# pc_tinyecg_max30001.net
KiCad netlist of a schematic drawn in EAGLE
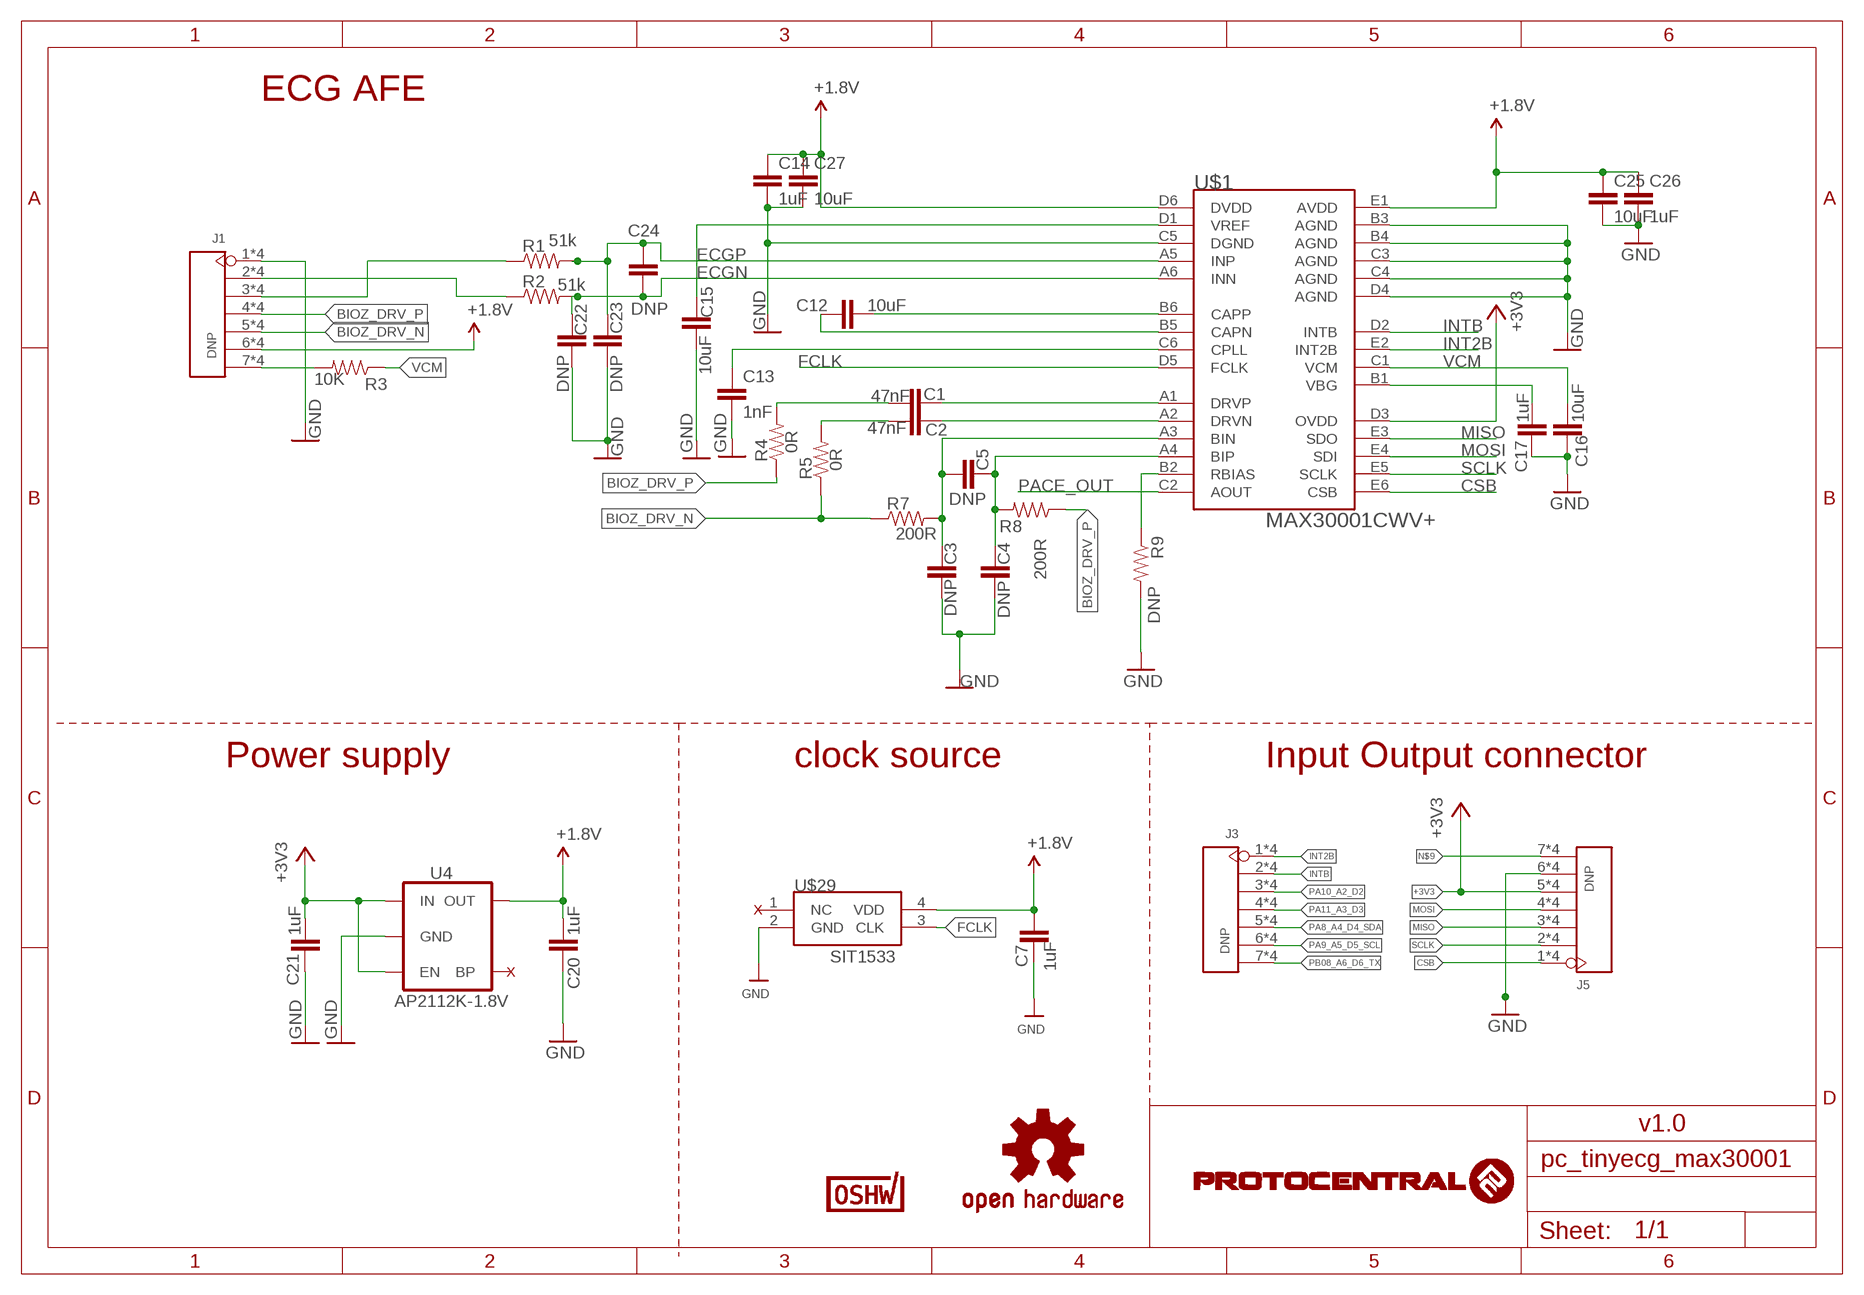
[diagram p0: schematic, sheet 1]

(export (version "E")
  (design (tool "Eeschema 10.0.6"))
  (components
    (comp (ref "C1")
      (value "47nF")
      (footprint "eagle-import:C0402")
      (libsource (lib "eagle-import") (part "C-EUC0402"))
    )
    (comp (ref "C2")
      (value "47nF")
      (footprint "eagle-import:C0402")
      (libsource (lib "eagle-import") (part "C-EUC0402"))
    )
    (comp (ref "C3")
      (value "DNP")
      (footprint "eagle-import:C0402")
      (libsource (lib "eagle-import") (part "C-EUC0402"))
    )
    (comp (ref "C4")
      (value "DNP")
      (footprint "eagle-import:C0402")
      (libsource (lib "eagle-import") (part "C-EUC0402"))
    )
    (comp (ref "C5")
      (value "DNP")
      (footprint "eagle-import:C0402")
      (libsource (lib "eagle-import") (part "C-EUC0402"))
    )
    (comp (ref "C7")
      (value "1uF")
      (footprint "eagle-import:C0402")
      (libsource (lib "eagle-import") (part "C-EUC0402"))
    )
    (comp (ref "C12")
      (value "10uF")
      (footprint "eagle-import:C0402")
      (libsource (lib "eagle-import") (part "C-EUC0402"))
    )
    (comp (ref "C13")
      (value "1nF")
      (footprint "eagle-import:C0402")
      (libsource (lib "eagle-import") (part "C-EUC0402"))
    )
    (comp (ref "C14")
      (value "1uF")
      (footprint "eagle-import:C0402")
      (libsource (lib "eagle-import") (part "C-EUC0402"))
    )
    (comp (ref "C15")
      (value "10uF")
      (footprint "eagle-import:C0402")
      (libsource (lib "eagle-import") (part "C-EUC0402"))
    )
    (comp (ref "C16")
      (value "10uF")
      (footprint "eagle-import:C0402")
      (libsource (lib "eagle-import") (part "C-EUC0402"))
    )
    (comp (ref "C17")
      (value "1uF")
      (footprint "eagle-import:C0402")
      (libsource (lib "eagle-import") (part "C-EUC0402"))
    )
    (comp (ref "C20")
      (value "1uF")
      (footprint "eagle-import:C0402")
      (libsource (lib "eagle-import") (part "C-EUC0402"))
    )
    (comp (ref "C21")
      (value "1uF")
      (footprint "eagle-import:C0402")
      (libsource (lib "eagle-import") (part "C-EUC0402"))
    )
    (comp (ref "C22")
      (value "DNP")
      (footprint "eagle-import:C0402")
      (libsource (lib "eagle-import") (part "C-EUC0402"))
    )
    (comp (ref "C23")
      (value "DNP")
      (footprint "eagle-import:C0402")
      (libsource (lib "eagle-import") (part "C-EUC0402"))
    )
    (comp (ref "C24")
      (value "DNP")
      (footprint "eagle-import:C0402")
      (libsource (lib "eagle-import") (part "C-EUC0402"))
    )
    (comp (ref "C25")
      (value "10uF")
      (footprint "eagle-import:C0402")
      (libsource (lib "eagle-import") (part "C-EUC0402"))
    )
    (comp (ref "C26")
      (value "1uF")
      (footprint "eagle-import:C0402")
      (libsource (lib "eagle-import") (part "C-EUC0402"))
    )
    (comp (ref "C27")
      (value "10uF")
      (footprint "eagle-import:C0402")
      (libsource (lib "eagle-import") (part "C-EUC0402"))
    )
    (comp (ref "J1")
      (value "DNP")
      (footprint "eagle-import:H7-HALF-HOLE-2.54")
      (libsource (lib "eagle-import") (part "HEADER-7P-HALF-HOLE-2.54"))
    )
    (comp (ref "J3")
      (value "DNP")
      (footprint "eagle-import:H7-HALF-HOLE-2.54")
      (libsource (lib "eagle-import") (part "HEADER-7P-HALF-HOLE-2.54"))
    )
    (comp (ref "J5")
      (value "DNP")
      (footprint "eagle-import:H7-HALF-HOLE-2.54")
      (libsource (lib "eagle-import") (part "HEADER-7P-HALF-HOLE-2.54"))
    )
    (comp (ref "R1")
      (value "51k")
      (footprint "eagle-import:0402-RES")
      (libsource (lib "eagle-import") (part "RESISTOR0402-RES"))
    )
    (comp (ref "R2")
      (value "51k")
      (footprint "eagle-import:0402-RES")
      (libsource (lib "eagle-import") (part "RESISTOR0402-RES"))
    )
    (comp (ref "R3")
      (value "10K")
      (footprint "eagle-import:0402-RES")
      (libsource (lib "eagle-import") (part "RESISTOR0402-RES"))
    )
    (comp (ref "R4")
      (value "0R")
      (footprint "eagle-import:0402-RES")
      (libsource (lib "eagle-import") (part "RESISTOR0402-RES"))
    )
    (comp (ref "R5")
      (value "0R")
      (footprint "eagle-import:0402-RES")
      (libsource (lib "eagle-import") (part "RESISTOR0402-RES"))
    )
    (comp (ref "R7")
      (value "200R")
      (footprint "eagle-import:0402-RES")
      (libsource (lib "eagle-import") (part "RESISTOR0402-RES"))
    )
    (comp (ref "R8")
      (value "200R")
      (footprint "eagle-import:0402-RES")
      (libsource (lib "eagle-import") (part "RESISTOR0402-RES"))
    )
    (comp (ref "R9")
      (value "DNP")
      (footprint "eagle-import:0402-RES")
      (libsource (lib "eagle-import") (part "RESISTOR0402-RES"))
    )
    (comp (ref "U$1")
      (value "MAX30001CWV+")
      (footprint "eagle-import:30WLP")
      (libsource (lib "eagle-import") (part "MAX30001CWV+"))
    )
    (comp (ref "U$14")
      (value "OSHW-LOGOM")
      (footprint "eagle-import:OSHW-LOGO-M")
      (libsource (lib "eagle-import") (part "OSHW-LOGOM"))
    )
    (comp (ref "U$29")
      (value "SIT1533")
      (footprint "eagle-import:SIT1533")
      (libsource (lib "eagle-import") (part "SIT1533"))
    )
    (comp (ref "U$35")
      (value "CERT-SMALL")
      (footprint "eagle-import:CERT-SMALL-SILK")
      (libsource (lib "eagle-import") (part "CERT-SMALL"))
    )
    (comp (ref "U4")
      (value "AP2112K-1.8V")
      (footprint "eagle-import:SOT23-5")
      (libsource (lib "eagle-import") (part "V_REG_LDOSMD"))
    )
  )
  (nets
    (net (code "1") (name "+1.8V") (class "Default")
      (node (ref "C14") (pin "1") (pinfunction "1_1") (pintype "passive"))
      (node (ref "C20") (pin "2") (pinfunction "2_2") (pintype "passive"))
      (node (ref "C25") (pin "1") (pinfunction "1_1") (pintype "passive"))
      (node (ref "C26") (pin "1") (pinfunction "1_1") (pintype "passive"))
      (node (ref "C27") (pin "1") (pinfunction "1_1") (pintype "passive"))
      (node (ref "C7") (pin "2") (pinfunction "2_2") (pintype "passive"))
      (node (ref "J1") (pin "18") (pinfunction "6_18") (pintype "bidirectional"))
      (node (ref "J1") (pin "6") (pinfunction "6_6") (pintype "bidirectional"))
      (node (ref "J1") (pin "P$6") (pinfunction "6_P$6") (pintype "bidirectional"))
      (node (ref "J1") (pin "P$9") (pinfunction "6_P$9") (pintype "bidirectional"))
      (node (ref "U$1") (pin "D6") (pinfunction "DVDD_D6") (pintype "bidirectional"))
      (node (ref "U$1") (pin "E1") (pinfunction "AVDD_E1") (pintype "bidirectional"))
      (node (ref "U$29") (pin "4") (pinfunction "VDD_4") (pintype "bidirectional"))
      (node (ref "U4") (pin "5") (pinfunction "OUT_5") (pintype "passive"))
    )
    (net (code "2") (name "+3V3") (class "Default")
      (node (ref "C21") (pin "2") (pinfunction "2_2") (pintype "passive"))
      (node (ref "J5") (pin "17") (pinfunction "5_17") (pintype "bidirectional"))
      (node (ref "J5") (pin "5") (pinfunction "5_5") (pintype "bidirectional"))
      (node (ref "J5") (pin "P$10") (pinfunction "5_P$10") (pintype "bidirectional"))
      (node (ref "J5") (pin "P$5") (pinfunction "5_P$5") (pintype "bidirectional"))
      (node (ref "U$1") (pin "D3") (pinfunction "OVDD_D3") (pintype "bidirectional"))
      (node (ref "U4") (pin "1") (pinfunction "IN_1") (pintype "input"))
      (node (ref "U4") (pin "3") (pinfunction "EN_3") (pintype "input"))
    )
    (net (code "3") (name "/ECGN") (class "Default")
      (node (ref "C22") (pin "1") (pinfunction "1_1") (pintype "passive"))
      (node (ref "C24") (pin "2") (pinfunction "2_2") (pintype "passive"))
      (node (ref "R2") (pin "2") (pinfunction "2_2") (pintype "passive"))
      (node (ref "U$1") (pin "A6") (pinfunction "INN_A6") (pintype "bidirectional"))
    )
    (net (code "4") (name "/ECGP") (class "Default")
      (node (ref "C23") (pin "1") (pinfunction "1_1") (pintype "passive"))
      (node (ref "C24") (pin "1") (pinfunction "1_1") (pintype "passive"))
      (node (ref "R1") (pin "2") (pinfunction "2_2") (pintype "passive"))
      (node (ref "U$1") (pin "A5") (pinfunction "INP_A5") (pintype "bidirectional"))
    )
    (net (code "5") (name "/PACE_OUT") (class "Default")
      (node (ref "U$1") (pin "C2") (pinfunction "AOUT_C2") (pintype "bidirectional"))
    )
    (net (code "6") (name "BIOZ_DRV_N") (class "Default")
      (node (ref "J1") (pin "17") (pinfunction "5_17") (pintype "bidirectional"))
      (node (ref "J1") (pin "5") (pinfunction "5_5") (pintype "bidirectional"))
      (node (ref "J1") (pin "P$10") (pinfunction "5_P$10") (pintype "bidirectional"))
      (node (ref "J1") (pin "P$5") (pinfunction "5_P$5") (pintype "bidirectional"))
      (node (ref "R5") (pin "1") (pinfunction "1_1") (pintype "passive"))
      (node (ref "R7") (pin "1") (pinfunction "1_1") (pintype "passive"))
    )
    (net (code "7") (name "BIOZ_DRV_P") (class "Default")
      (node (ref "J1") (pin "16") (pinfunction "4_16") (pintype "bidirectional"))
      (node (ref "J1") (pin "4") (pinfunction "4_4") (pintype "bidirectional"))
      (node (ref "J1") (pin "P$11") (pinfunction "4_P$11") (pintype "bidirectional"))
      (node (ref "J1") (pin "P$4") (pinfunction "4_P$4") (pintype "bidirectional"))
      (node (ref "R4") (pin "1") (pinfunction "1_1") (pintype "passive"))
      (node (ref "R8") (pin "1") (pinfunction "1_1") (pintype "passive"))
    )
    (net (code "8") (name "CSB") (class "Default")
      (node (ref "J5") (pin "1") (pinfunction "1_1") (pintype "bidirectional"))
      (node (ref "J5") (pin "13") (pinfunction "1_13") (pintype "bidirectional"))
      (node (ref "J5") (pin "P$1") (pinfunction "1_P$1") (pintype "bidirectional"))
      (node (ref "J5") (pin "P$14") (pinfunction "1_P$14") (pintype "bidirectional"))
      (node (ref "U$1") (pin "E6") (pinfunction "CSB_E6") (pintype "bidirectional"))
    )
    (net (code "9") (name "FCLK") (class "Default")
      (node (ref "U$1") (pin "D5") (pinfunction "FCLK_D5") (pintype "bidirectional"))
      (node (ref "U$29") (pin "3") (pinfunction "CLK_3") (pintype "bidirectional"))
    )
    (net (code "10") (name "GND") (class "Default")
      (node (ref "C13") (pin "2") (pinfunction "2_2") (pintype "passive"))
      (node (ref "C14") (pin "2") (pinfunction "2_2") (pintype "passive"))
      (node (ref "C15") (pin "2") (pinfunction "2_2") (pintype "passive"))
      (node (ref "C16") (pin "2") (pinfunction "2_2") (pintype "passive"))
      (node (ref "C17") (pin "2") (pinfunction "2_2") (pintype "passive"))
      (node (ref "C20") (pin "1") (pinfunction "1_1") (pintype "passive"))
      (node (ref "C21") (pin "1") (pinfunction "1_1") (pintype "passive"))
      (node (ref "C22") (pin "2") (pinfunction "2_2") (pintype "passive"))
      (node (ref "C23") (pin "2") (pinfunction "2_2") (pintype "passive"))
      (node (ref "C25") (pin "2") (pinfunction "2_2") (pintype "passive"))
      (node (ref "C26") (pin "2") (pinfunction "2_2") (pintype "passive"))
      (node (ref "C27") (pin "2") (pinfunction "2_2") (pintype "passive"))
      (node (ref "C3") (pin "2") (pinfunction "2_2") (pintype "passive"))
      (node (ref "C4") (pin "2") (pinfunction "2_2") (pintype "passive"))
      (node (ref "C7") (pin "1") (pinfunction "1_1") (pintype "passive"))
      (node (ref "J1") (pin "1") (pinfunction "1_1") (pintype "bidirectional"))
      (node (ref "J1") (pin "13") (pinfunction "1_13") (pintype "bidirectional"))
      (node (ref "J1") (pin "P$1") (pinfunction "1_P$1") (pintype "bidirectional"))
      (node (ref "J1") (pin "P$14") (pinfunction "1_P$14") (pintype "bidirectional"))
      (node (ref "J5") (pin "18") (pinfunction "6_18") (pintype "bidirectional"))
      (node (ref "J5") (pin "6") (pinfunction "6_6") (pintype "bidirectional"))
      (node (ref "J5") (pin "P$6") (pinfunction "6_P$6") (pintype "bidirectional"))
      (node (ref "J5") (pin "P$9") (pinfunction "6_P$9") (pintype "bidirectional"))
      (node (ref "R9") (pin "2") (pinfunction "2_2") (pintype "passive"))
      (node (ref "U$1") (pin "B3") (pinfunction "AGND_B3") (pintype "bidirectional"))
      (node (ref "U$1") (pin "B4") (pinfunction "AGND_B4") (pintype "bidirectional"))
      (node (ref "U$1") (pin "C3") (pinfunction "AGND_C3") (pintype "bidirectional"))
      (node (ref "U$1") (pin "C4") (pinfunction "AGND_C4") (pintype "bidirectional"))
      (node (ref "U$1") (pin "C5") (pinfunction "DGND_C5") (pintype "bidirectional"))
      (node (ref "U$1") (pin "D4") (pinfunction "AGND_D4") (pintype "bidirectional"))
      (node (ref "U$29") (pin "2") (pinfunction "GND_2") (pintype "bidirectional"))
      (node (ref "U4") (pin "2") (pinfunction "GND_2") (pintype "input"))
    )
    (net (code "11") (name "INT2B") (class "Default")
      (node (ref "J3") (pin "1") (pinfunction "1_1") (pintype "bidirectional"))
      (node (ref "J3") (pin "13") (pinfunction "1_13") (pintype "bidirectional"))
      (node (ref "J3") (pin "P$1") (pinfunction "1_P$1") (pintype "bidirectional"))
      (node (ref "J3") (pin "P$14") (pinfunction "1_P$14") (pintype "bidirectional"))
      (node (ref "U$1") (pin "E2") (pinfunction "INT2B_E2") (pintype "bidirectional"))
    )
    (net (code "12") (name "INTB") (class "Default")
      (node (ref "J3") (pin "14") (pinfunction "2_14") (pintype "bidirectional"))
      (node (ref "J3") (pin "2") (pinfunction "2_2") (pintype "bidirectional"))
      (node (ref "J3") (pin "P$13") (pinfunction "2_P$13") (pintype "bidirectional"))
      (node (ref "J3") (pin "P$2") (pinfunction "2_P$2") (pintype "bidirectional"))
      (node (ref "U$1") (pin "D2") (pinfunction "INTB_D2") (pintype "bidirectional"))
    )
    (net (code "13") (name "MISO") (class "Default")
      (node (ref "J5") (pin "15") (pinfunction "3_15") (pintype "bidirectional"))
      (node (ref "J5") (pin "3") (pinfunction "3_3") (pintype "bidirectional"))
      (node (ref "J5") (pin "P$12") (pinfunction "3_P$12") (pintype "bidirectional"))
      (node (ref "J5") (pin "P$3") (pinfunction "3_P$3") (pintype "bidirectional"))
      (node (ref "U$1") (pin "E3") (pinfunction "SDO_E3") (pintype "bidirectional"))
    )
    (net (code "14") (name "MOSI") (class "Default")
      (node (ref "J5") (pin "16") (pinfunction "4_16") (pintype "bidirectional"))
      (node (ref "J5") (pin "4") (pinfunction "4_4") (pintype "bidirectional"))
      (node (ref "J5") (pin "P$11") (pinfunction "4_P$11") (pintype "bidirectional"))
      (node (ref "J5") (pin "P$4") (pinfunction "4_P$4") (pintype "bidirectional"))
      (node (ref "U$1") (pin "E4") (pinfunction "SDI_E4") (pintype "bidirectional"))
    )
    (net (code "15") (name "N$9") (class "Default")
      (node (ref "J5") (pin "19") (pinfunction "7_19") (pintype "bidirectional"))
      (node (ref "J5") (pin "7") (pinfunction "7_7") (pintype "bidirectional"))
      (node (ref "J5") (pin "P$7") (pinfunction "7_P$7") (pintype "bidirectional"))
      (node (ref "J5") (pin "P$8") (pinfunction "7_P$8") (pintype "bidirectional"))
    )
    (net (code "16") (name "Net-(C1-Pad1)") (class "Default")
      (node (ref "C1") (pin "1") (pinfunction "1_1") (pintype "passive"))
      (node (ref "R4") (pin "2") (pinfunction "2_2") (pintype "passive"))
    )
    (net (code "17") (name "Net-(C2-Pad1)") (class "Default")
      (node (ref "C2") (pin "1") (pinfunction "1_1") (pintype "passive"))
      (node (ref "R5") (pin "2") (pinfunction "2_2") (pintype "passive"))
    )
    (net (code "18") (name "Net-(J1-2-Pad14)") (class "Default")
      (node (ref "J1") (pin "14") (pinfunction "2_14") (pintype "bidirectional"))
      (node (ref "J1") (pin "2") (pinfunction "2_2") (pintype "bidirectional"))
      (node (ref "J1") (pin "P$13") (pinfunction "2_P$13") (pintype "bidirectional"))
      (node (ref "J1") (pin "P$2") (pinfunction "2_P$2") (pintype "bidirectional"))
      (node (ref "R2") (pin "1") (pinfunction "1_1") (pintype "passive"))
    )
    (net (code "19") (name "Net-(J1-3-Pad15)") (class "Default")
      (node (ref "J1") (pin "15") (pinfunction "3_15") (pintype "bidirectional"))
      (node (ref "J1") (pin "3") (pinfunction "3_3") (pintype "bidirectional"))
      (node (ref "J1") (pin "P$12") (pinfunction "3_P$12") (pintype "bidirectional"))
      (node (ref "J1") (pin "P$3") (pinfunction "3_P$3") (pintype "bidirectional"))
      (node (ref "R1") (pin "1") (pinfunction "1_1") (pintype "passive"))
    )
    (net (code "20") (name "Net-(J1-7-Pad19)") (class "Default")
      (node (ref "J1") (pin "19") (pinfunction "7_19") (pintype "bidirectional"))
      (node (ref "J1") (pin "7") (pinfunction "7_7") (pintype "bidirectional"))
      (node (ref "J1") (pin "P$7") (pinfunction "7_P$7") (pintype "bidirectional"))
      (node (ref "J1") (pin "P$8") (pinfunction "7_P$8") (pintype "bidirectional"))
      (node (ref "R3") (pin "2") (pinfunction "2_2") (pintype "passive"))
    )
    (net (code "21") (name "Net-(U$1-BIN)") (class "Default")
      (node (ref "C3") (pin "1") (pinfunction "1_1") (pintype "passive"))
      (node (ref "C5") (pin "1") (pinfunction "1_1") (pintype "passive"))
      (node (ref "R7") (pin "2") (pinfunction "2_2") (pintype "passive"))
      (node (ref "U$1") (pin "A3") (pinfunction "BIN_A3") (pintype "bidirectional"))
    )
    (net (code "22") (name "Net-(U$1-BIP)") (class "Default")
      (node (ref "C4") (pin "1") (pinfunction "1_1") (pintype "passive"))
      (node (ref "C5") (pin "2") (pinfunction "2_2") (pintype "passive"))
      (node (ref "R8") (pin "2") (pinfunction "2_2") (pintype "passive"))
      (node (ref "U$1") (pin "A4") (pinfunction "BIP_A4") (pintype "bidirectional"))
    )
    (net (code "23") (name "Net-(U$1-CAPN)") (class "Default")
      (node (ref "C12") (pin "2") (pinfunction "2_2") (pintype "passive"))
      (node (ref "U$1") (pin "B5") (pinfunction "CAPN_B5") (pintype "bidirectional"))
    )
    (net (code "24") (name "Net-(U$1-CAPP)") (class "Default")
      (node (ref "C12") (pin "1") (pinfunction "1_1") (pintype "passive"))
      (node (ref "U$1") (pin "B6") (pinfunction "CAPP_B6") (pintype "bidirectional"))
    )
    (net (code "25") (name "Net-(U$1-CPLL)") (class "Default")
      (node (ref "C13") (pin "1") (pinfunction "1_1") (pintype "passive"))
      (node (ref "U$1") (pin "C6") (pinfunction "CPLL_C6") (pintype "bidirectional"))
    )
    (net (code "26") (name "Net-(U$1-DRVN)") (class "Default")
      (node (ref "C2") (pin "2") (pinfunction "2_2") (pintype "passive"))
      (node (ref "U$1") (pin "A2") (pinfunction "DRVN_A2") (pintype "bidirectional"))
    )
    (net (code "27") (name "Net-(U$1-DRVP)") (class "Default")
      (node (ref "C1") (pin "2") (pinfunction "2_2") (pintype "passive"))
      (node (ref "U$1") (pin "A1") (pinfunction "DRVP_A1") (pintype "bidirectional"))
    )
    (net (code "28") (name "Net-(U$1-RBIAS)") (class "Default")
      (node (ref "R9") (pin "1") (pinfunction "1_1") (pintype "passive"))
      (node (ref "U$1") (pin "B2") (pinfunction "RBIAS_B2") (pintype "bidirectional"))
    )
    (net (code "29") (name "Net-(U$1-VBG)") (class "Default")
      (node (ref "C17") (pin "1") (pinfunction "1_1") (pintype "passive"))
      (node (ref "U$1") (pin "B1") (pinfunction "VBG_B1") (pintype "bidirectional"))
    )
    (net (code "30") (name "Net-(U$1-VREF)") (class "Default")
      (node (ref "C15") (pin "1") (pinfunction "1_1") (pintype "passive"))
      (node (ref "U$1") (pin "D1") (pinfunction "VREF_D1") (pintype "bidirectional"))
    )
    (net (code "31") (name "PA8_A4_D4_SDA") (class "Default")
      (node (ref "J3") (pin "17") (pinfunction "5_17") (pintype "bidirectional"))
      (node (ref "J3") (pin "5") (pinfunction "5_5") (pintype "bidirectional"))
      (node (ref "J3") (pin "P$10") (pinfunction "5_P$10") (pintype "bidirectional"))
      (node (ref "J3") (pin "P$5") (pinfunction "5_P$5") (pintype "bidirectional"))
    )
    (net (code "32") (name "PA9_A5_D5_SCL") (class "Default")
      (node (ref "J3") (pin "18") (pinfunction "6_18") (pintype "bidirectional"))
      (node (ref "J3") (pin "6") (pinfunction "6_6") (pintype "bidirectional"))
      (node (ref "J3") (pin "P$6") (pinfunction "6_P$6") (pintype "bidirectional"))
      (node (ref "J3") (pin "P$9") (pinfunction "6_P$9") (pintype "bidirectional"))
    )
    (net (code "33") (name "PA10_A2_D2") (class "Default")
      (node (ref "J3") (pin "15") (pinfunction "3_15") (pintype "bidirectional"))
      (node (ref "J3") (pin "3") (pinfunction "3_3") (pintype "bidirectional"))
      (node (ref "J3") (pin "P$12") (pinfunction "3_P$12") (pintype "bidirectional"))
      (node (ref "J3") (pin "P$3") (pinfunction "3_P$3") (pintype "bidirectional"))
    )
    (net (code "34") (name "PA11_A3_D3") (class "Default")
      (node (ref "J3") (pin "16") (pinfunction "4_16") (pintype "bidirectional"))
      (node (ref "J3") (pin "4") (pinfunction "4_4") (pintype "bidirectional"))
      (node (ref "J3") (pin "P$11") (pinfunction "4_P$11") (pintype "bidirectional"))
      (node (ref "J3") (pin "P$4") (pinfunction "4_P$4") (pintype "bidirectional"))
    )
    (net (code "35") (name "PB08_A6_D6_TX") (class "Default")
      (node (ref "J3") (pin "19") (pinfunction "7_19") (pintype "bidirectional"))
      (node (ref "J3") (pin "7") (pinfunction "7_7") (pintype "bidirectional"))
      (node (ref "J3") (pin "P$7") (pinfunction "7_P$7") (pintype "bidirectional"))
      (node (ref "J3") (pin "P$8") (pinfunction "7_P$8") (pintype "bidirectional"))
    )
    (net (code "36") (name "SCLK") (class "Default")
      (node (ref "J5") (pin "14") (pinfunction "2_14") (pintype "bidirectional"))
      (node (ref "J5") (pin "2") (pinfunction "2_2") (pintype "bidirectional"))
      (node (ref "J5") (pin "P$13") (pinfunction "2_P$13") (pintype "bidirectional"))
      (node (ref "J5") (pin "P$2") (pinfunction "2_P$2") (pintype "bidirectional"))
      (node (ref "U$1") (pin "E5") (pinfunction "SCLK_E5") (pintype "bidirectional"))
    )
    (net (code "37") (name "VCM") (class "Default")
      (node (ref "C16") (pin "1") (pinfunction "1_1") (pintype "passive"))
      (node (ref "R3") (pin "1") (pinfunction "1_1") (pintype "passive"))
      (node (ref "U$1") (pin "C1") (pinfunction "VCM_C1") (pintype "bidirectional"))
    )
    (net (code "38") (name "unconnected-(U$29-NC-Pad1)") (class "Default")
      (node (ref "U$29") (pin "1") (pinfunction "NC_1") (pintype "bidirectional"))
    )
    (net (code "39") (name "unconnected-(U4-BP-Pad4)") (class "Default")
      (node (ref "U4") (pin "4") (pinfunction "BP_4") (pintype "input"))
    )
  )
)
